# Charging.net
KiCad netlist of a schematic drawn in Altium Designer
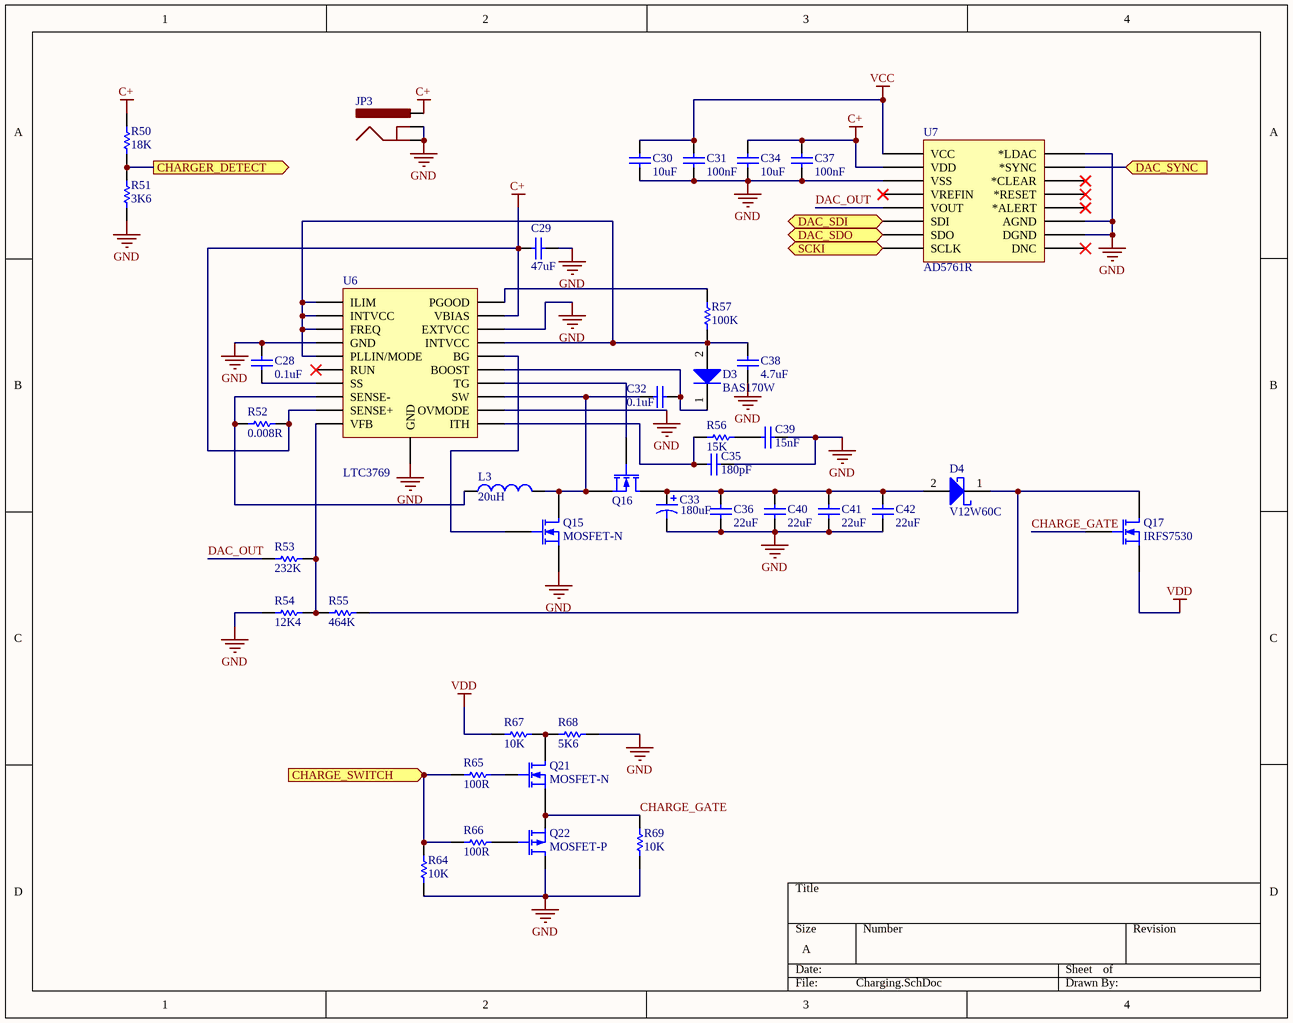
[diagram p0: Charging.SchDoc]

(export (version "E")
  (design (tool "Eeschema 10.0.6"))
  (components
    (comp (ref "C28")
      (value "0.1uF")
      (footprint "CAPC0603(1608)100_N")
      (description "CAP 100nF 6.3V Â±5% 0603 (1608 Metric) Thickness 1mm SMD")
      (fields (field (name "TOLERANCE") "Â±5%"))
      (libsource (lib "Altium Content Vault") (part "CAP"))
    )
    (comp (ref "C29")
      (value "47uF")
      (footprint "CAPC1206(3216)190_N")
      (description "CAP 22uF 25V Â±20% 1206 (3216 Metric) Thickness 1.9mm SMD")
      (fields (field (name "TOLERANCE") "Â±20%"))
      (libsource (lib "Altium Content Vault") (part "CMP-1037-04995-1"))
    )
    (comp (ref "C30")
      (value "10uF")
      (footprint "CAPC0805(2012)145_M")
      (description "CAP 10uF 25V Â±10% 0805 (2012 Metric) Thickness 1.45mm SMD")
      (fields (field (name "TOLERANCE") "Â±10%"))
      (libsource (lib "Altium Content Vault") (part "CAP"))
    )
    (comp (ref "C31")
      (value "100nF")
      (footprint "CAPC0603(1608)100_L")
      (description "CAP 100nF 25V Â±5% 0603 (1608 Metric) Thickness 1mm SMD")
      (fields (field (name "TOLERANCE") "Â±5%"))
      (libsource (lib "Altium Content Vault") (part "CAP"))
    )
    (comp (ref "C32")
      (value "0.1uF")
      (footprint "CAPC0603(1608)100_N")
      (description "CAP 100nF 6.3V Â±5% 0603 (1608 Metric) Thickness 1mm SMD")
      (fields (field (name "TOLERANCE") "Â±5%"))
      (libsource (lib "Altium Content Vault") (part "CAP"))
    )
    (comp (ref "C33")
      (value "180uF")
      (footprint "CAP 180uF 50V")
      (description "Polarized Capacitor (Axial)")
      (fields (field (name "PUBLISHER") "Altium Limited"))
      (libsource (lib "Components") (part "CAP 180uF 50V"))
    )
    (comp (ref "C34")
      (value "10uF")
      (footprint "CAPC0805(2012)145_M")
      (description "CAP 10uF 25V Â±10% 0805 (2012 Metric) Thickness 1.45mm SMD")
      (fields (field (name "TOLERANCE") "Â±10%"))
      (libsource (lib "Altium Content Vault") (part "CAP"))
    )
    (comp (ref "C35")
      (value "180pF")
      (footprint "CAPC0603(1608)100_L")
      (description "CAP 180pF 6.3V Â±5% 0603 (1608 Metric) Thickness 1mm SMD")
      (fields (field (name "TOLERANCE") "Â±5%"))
      (libsource (lib "Altium Content Vault") (part "CAP"))
    )
    (comp (ref "C36")
      (value "22uF")
      (footprint "CAPC2220(5750)230_L")
      (description "CAP 22uF 50V -20% to +80% 2220 (5750 Metric) Thickness 2.2mm SMD")
      (fields (field (name "TOLERANCE") "-20% to +80%"))
      (libsource (lib "Altium Content Vault") (part "CAP"))
    )
    (comp (ref "C37")
      (value "100nF")
      (footprint "CAPC0603(1608)100_L")
      (description "CAP 100nF 25V Â±5% 0603 (1608 Metric) Thickness 1mm SMD")
      (fields (field (name "TOLERANCE") "Â±5%"))
      (libsource (lib "Altium Content Vault") (part "CAP"))
    )
    (comp (ref "C38")
      (value "4.7uF")
      (footprint "CAPC0603(1608)55_L")
      (description "CAP 4.7uF 6.3V Â±10% 0603 (1608 Metric) Thickness 0.55mm SMD")
      (fields (field (name "TOLERANCE") "Â±10%"))
      (libsource (lib "Altium Content Vault") (part "CAP"))
    )
    (comp (ref "C39")
      (value "15nF")
      (footprint "CAPC0603(1608)100_M")
      (description "CAP 15nF 6.3V Â±5% 0603 (1608 Metric) Thickness 1mm SMD")
      (fields (field (name "TOLERANCE") "Â±5%"))
      (libsource (lib "Altium Content Vault") (part "CAP"))
    )
    (comp (ref "C40")
      (value "22uF")
      (footprint "CAPC2220(5750)230_L")
      (description "CAP 22uF 50V -20% to +80% 2220 (5750 Metric) Thickness 2.2mm SMD")
      (fields (field (name "TOLERANCE") "-20% to +80%"))
      (libsource (lib "Altium Content Vault") (part "CAP"))
    )
    (comp (ref "C41")
      (value "22uF")
      (footprint "CAPC2220(5750)230_L")
      (description "CAP 22uF 50V -20% to +80% 2220 (5750 Metric) Thickness 2.2mm SMD")
      (fields (field (name "TOLERANCE") "-20% to +80%"))
      (libsource (lib "Altium Content Vault") (part "CAP"))
    )
    (comp (ref "C42")
      (value "22uF")
      (footprint "CAPC2220(5750)230_L")
      (description "CAP 22uF 50V -20% to +80% 2220 (5750 Metric) Thickness 2.2mm SMD")
      (fields (field (name "TOLERANCE") "-20% to +80%"))
      (libsource (lib "Altium Content Vault") (part "CAP"))
    )
    (comp (ref "D3")
      (value "BAS170W")
      (footprint "INF-SOD323_V")
      (description "Silicon Schottky Diode, -55 to 125 degC, SOD323, Reel, Green")
      (fields (field (name "MANUFACTURER") "Infineon"))
      (libsource (lib "Altium Content Vault") (part "INF-D_K1A2-2"))
    )
    (comp (ref "D4")
      (value "V12W60C")
      (footprint "DPAK229P1003X238-3N")
      (libsource (lib "Components") (part "V12W60C"))
    )
    (comp (ref "JP3")
      (value "~")
      (footprint "POWER_JACK_SMD_OVERPASTE_REDBOARD_0603")
      (libsource (lib "SparkFun-Connectors") (part "POWER_JACK1"))
    )
    (comp (ref "L3")
      (value "20uH")
      (footprint "Inductor_LR")
      (description "Inductor")
      (fields (field (name "PUBLISHER") "Altium Limited"))
      (libsource (lib "Components") (part "CTX20-7-52LP-R"))
    )
    (comp (ref "Q15")
      (value "MOSFET-N")
      (footprint "SOIC127P600X175-8N")
      (description "N-Channel MOSFET")
      (fields (field (name "PUBLISHER") "Altium Limited"))
      (libsource (lib "Components") (part "MOSFET-N"))
    )
    (comp (ref "Q16")
      (value "~")
      (footprint "SOIC127P600X175-8N")
      (description "N-Channel MOSFET")
      (fields (field (name "PUBLISHER") "Altium Limited"))
      (libsource (lib "Components") (part "MOSFET-N"))
    )
    (comp (ref "Q17")
      (value "IRFS7530")
      (footprint "DPAK127P1525X483-7N")
      (description "N-Channel MOSFET")
      (fields (field (name "PUBLISHER") "Altium Limited"))
      (libsource (lib "Components") (part "IRFS7530"))
    )
    (comp (ref "Q21")
      (value "MOSFET-N")
      (footprint "SOT23-3")
      (description "N-Channel MOSFET")
      (fields (field (name "PUBLISHER") "Altium Limited"))
      (libsource (lib "Components") (part "MOSFET-N"))
    )
    (comp (ref "Q22")
      (value "MOSFET-P")
      (footprint "SOT23-3")
      (description "P-Channel MOSFET")
      (fields (field (name "PUBLISHER") "Altium Limited"))
      (libsource (lib "Components") (part "MOSFET-P"))
    )
    (comp (ref "R50")
      (value "18K")
      (footprint "RESC0603(1608)_L")
      (description "18K 0.1W 1% 0603 (1608 Metric)  SMD")
      (fields (field (name "POWER") "0.1 W") (field (name "TOLERANCE") "1 %"))
      (libsource (lib "Altium Content Vault") (part "RES"))
    )
    (comp (ref "R51")
      (value "3K6")
      (footprint "RESC0603(1608)_M")
      (description "3K6 0.1W 1% 0603 (1608 Metric)  SMD")
      (fields (field (name "TOLERANCE") "1 %") (field (name "POWER") "0.1 W"))
      (libsource (lib "Altium Content Vault") (part "RES"))
    )
    (comp (ref "R52")
      (value "0.008R")
      (footprint "RESC2010(5025)_N")
      (description "1R 0.75W 5% 2010 (5025 Metric)  SMD")
      (fields (field (name "TOLERANCE") "5 %") (field (name "POWER") "0.75 W"))
      (libsource (lib "Altium Content Vault") (part "CMP-1017-00002-1"))
    )
    (comp (ref "R53")
      (value "232K")
      (footprint "RESC0603(1608)_L")
      (description "232K 0.1W 1% 0603 (1608 Metric)  SMD")
      (fields (field (name "TOLERANCE") "1 %") (field (name "POWER") "0.1 W"))
      (libsource (lib "Altium Content Vault") (part "RES"))
    )
    (comp (ref "R54")
      (value "12K4")
      (footprint "RESC0603(1608)_L")
      (description "12K4 0.1W 1% 0603 (1608 Metric)  SMD")
      (fields (field (name "POWER") "0.1 W") (field (name "TOLERANCE") "1 %"))
      (libsource (lib "Altium Content Vault") (part "RES"))
    )
    (comp (ref "R55")
      (value "464K")
      (footprint "RESC0603(1608)_N")
      (description "464K 0.1W 1% 0603 (1608 Metric)  SMD")
      (fields (field (name "TOLERANCE") "1 %") (field (name "POWER") "0.1 W"))
      (libsource (lib "Altium Content Vault") (part "RES"))
    )
    (comp (ref "R56")
      (value "15K")
      (footprint "RESC0603(1608)_L")
      (description "15K 0.1W 5% 0603 (1608 Metric)  SMD")
      (fields (field (name "POWER") "0.1 W") (field (name "TOLERANCE") "5 %"))
      (libsource (lib "Altium Content Vault") (part "RES"))
    )
    (comp (ref "R57")
      (value "100K")
      (footprint "RESC0603(1608)_M")
      (description "100K 0.1W 5% 0603 (1608 Metric)  SMD")
      (fields (field (name "TOLERANCE") "5 %") (field (name "POWER") "0.1 W"))
      (libsource (lib "Altium Content Vault") (part "RES"))
    )
    (comp (ref "R64")
      (value "10K")
      (footprint "RESC0603(1608)_M")
      (description "10K 0.1W 1% 0603 (1608 Metric)  SMD")
      (fields (field (name "POWER") "0.1 W") (field (name "TOLERANCE") "1 %"))
      (libsource (lib "Altium Content Vault") (part "RES"))
    )
    (comp (ref "R65")
      (value "100R")
      (footprint "RESC0603(1608)_M")
      (description "100R 0.1W 5% 0603 (1608 Metric)  SMD")
      (fields (field (name "TOLERANCE") "5 %") (field (name "POWER") "0.1 W"))
      (libsource (lib "Altium Content Vault") (part "RES"))
    )
    (comp (ref "R66")
      (value "100R")
      (footprint "RESC0603(1608)_M")
      (description "100R 0.1W 5% 0603 (1608 Metric)  SMD")
      (fields (field (name "TOLERANCE") "5 %") (field (name "POWER") "0.1 W"))
      (libsource (lib "Altium Content Vault") (part "RES"))
    )
    (comp (ref "R67")
      (value "10K")
      (footprint "RESC0603(1608)_M")
      (description "10K 0.1W 5% 0603 (1608 Metric)  SMD")
      (fields (field (name "TOLERANCE") "5 %") (field (name "POWER") "0.1 W"))
      (libsource (lib "Altium Content Vault") (part "RES"))
    )
    (comp (ref "R68")
      (value "5K6")
      (footprint "RESC0603(1608)_N")
      (description "5K6 0.1W 1% 0603 (1608 Metric)  SMD")
      (fields (field (name "TOLERANCE") "1 %") (field (name "POWER") "0.1 W"))
      (libsource (lib "Altium Content Vault") (part "RES"))
    )
    (comp (ref "R69")
      (value "10K")
      (footprint "RESC0603(1608)_M")
      (description "10K 0.1W 1% 0603 (1608 Metric)  SMD")
      (fields (field (name "POWER") "0.1 W") (field (name "TOLERANCE") "1 %"))
      (libsource (lib "Altium Content Vault") (part "RES"))
    )
    (comp (ref "U6")
      (value "LTC3769")
      (footprint "TSOP65P640X120_HS-21N")
      (libsource (lib "Components") (part "LTC3769"))
    )
    (comp (ref "U7")
      (value "AD5761R")
      (footprint "RU_16")
      (description "Imported")
      (libsource (lib "Components") (part "AD5761BRUZ"))
    )
  )
  (nets
    (net (code "1") (name "/CHARGER_DETECT") (class "Default")
      (node (ref "R50") (pin "1") (pinfunction "1_1") (pintype "passive"))
      (node (ref "R51") (pin "2") (pinfunction "2_2") (pintype "passive"))
    )
    (net (code "2") (name "/CHARGE_GATE") (class "Default")
      (node (ref "Q17") (pin "2") (pinfunction "G_2") (pintype "passive"))
      (node (ref "Q21") (pin "3") (pinfunction "S_3") (pintype "passive"))
      (node (ref "Q22") (pin "3") (pinfunction "S_3") (pintype "passive"))
      (node (ref "R69") (pin "2") (pinfunction "2_2") (pintype "passive"))
    )
    (net (code "3") (name "/CHARGE_SWITCH") (class "Default")
      (node (ref "R64") (pin "2") (pinfunction "2_2") (pintype "passive"))
      (node (ref "R65") (pin "1") (pinfunction "1_1") (pintype "passive"))
      (node (ref "R66") (pin "1") (pinfunction "1_1") (pintype "passive"))
    )
    (net (code "4") (name "/DAC_OUT") (class "Default")
      (node (ref "R53") (pin "1") (pinfunction "1_1") (pintype "passive"))
      (node (ref "U7") (pin "7") (pinfunction "VOUT_7") (pintype "passive"))
    )
    (net (code "5") (name "/DAC_SDI") (class "Default")
      (node (ref "U7") (pin "12") (pinfunction "SDI_12") (pintype "passive"))
    )
    (net (code "6") (name "/DAC_SDO") (class "Default")
      (node (ref "U7") (pin "10") (pinfunction "SDO_10") (pintype "passive"))
    )
    (net (code "7") (name "/DAC_SYNC") (class "Default")
      (node (ref "U7") (pin "13") (pinfunction "*SYNC_13") (pintype "passive"))
    )
    (net (code "8") (name "/SCKI") (class "Default")
      (node (ref "U7") (pin "14") (pinfunction "SCLK_14") (pintype "passive"))
    )
    (net (code "9") (name "C+") (class "Default")
      (node (ref "C29") (pin "1") (pinfunction "1_1") (pintype "passive"))
      (node (ref "C34") (pin "2") (pinfunction "2_2") (pintype "passive"))
      (node (ref "C37") (pin "2") (pinfunction "2_2") (pintype "passive"))
      (node (ref "JP3") (pin "VIN0") (pinfunction "PWR_VIN0") (pintype "passive"))
      (node (ref "R50") (pin "2") (pinfunction "2_2") (pintype "passive"))
      (node (ref "R52") (pin "2") (pinfunction "2_2") (pintype "passive"))
      (node (ref "U6") (pin "19") (pinfunction "VBIAS_19") (pintype "passive"))
      (node (ref "U6") (pin "9") (pinfunction "SENSE+_9") (pintype "passive"))
      (node (ref "U7") (pin "8") (pinfunction "VDD_8") (pintype "passive"))
    )
    (net (code "10") (name "GND") (class "Default")
      (node (ref "C28") (pin "2") (pinfunction "2_2") (pintype "passive"))
      (node (ref "C29") (pin "2") (pinfunction "2_2") (pintype "passive"))
      (node (ref "C30") (pin "1") (pinfunction "1_1") (pintype "passive"))
      (node (ref "C31") (pin "1") (pinfunction "1_1") (pintype "passive"))
      (node (ref "C33") (pin "2") (pinfunction "2_2") (pintype "passive"))
      (node (ref "C34") (pin "1") (pinfunction "1_1") (pintype "passive"))
      (node (ref "C35") (pin "2") (pinfunction "2_2") (pintype "passive"))
      (node (ref "C36") (pin "1") (pinfunction "1_1") (pintype "passive"))
      (node (ref "C37") (pin "1") (pinfunction "1_1") (pintype "passive"))
      (node (ref "C38") (pin "1") (pinfunction "1_1") (pintype "passive"))
      (node (ref "C39") (pin "2") (pinfunction "2_2") (pintype "passive"))
      (node (ref "C40") (pin "1") (pinfunction "1_1") (pintype "passive"))
      (node (ref "C41") (pin "1") (pinfunction "1_1") (pintype "passive"))
      (node (ref "C42") (pin "1") (pinfunction "1_1") (pintype "passive"))
      (node (ref "JP3") (pin "GND") (pinfunction "GNDBREAK_GND") (pintype "passive"))
      (node (ref "JP3") (pin "P$4") (pinfunction "GND_P$4") (pintype "passive"))
      (node (ref "Q15") (pin "3") (pinfunction "S_3") (pintype "passive"))
      (node (ref "Q22") (pin "2") (pinfunction "D_2") (pintype "passive"))
      (node (ref "R51") (pin "1") (pinfunction "1_1") (pintype "passive"))
      (node (ref "R54") (pin "1") (pinfunction "1_1") (pintype "passive"))
      (node (ref "R64") (pin "1") (pinfunction "1_1") (pintype "passive"))
      (node (ref "R68") (pin "1") (pinfunction "1_1") (pintype "passive"))
      (node (ref "R69") (pin "1") (pinfunction "1_1") (pintype "passive"))
      (node (ref "U6") (pin "12") (pinfunction "OVMODE_12") (pintype "passive"))
      (node (ref "U6") (pin "18") (pinfunction "EXTVCC_18") (pintype "passive"))
      (node (ref "U6") (pin "21") (pinfunction "GND_21") (pintype "passive"))
      (node (ref "U6") (pin "4") (pinfunction "GND_4") (pintype "passive"))
      (node (ref "U7") (pin "11") (pinfunction "*LDAC_11") (pintype "passive"))
      (node (ref "U7") (pin "16") (pinfunction "DGND_16") (pintype "passive"))
      (node (ref "U7") (pin "5") (pinfunction "AGND_5") (pintype "passive"))
      (node (ref "U7") (pin "6") (pinfunction "VSS_6") (pintype "passive"))
    )
    (net (code "11") (name "Net-(C39-Pad1)") (class "Default")
      (node (ref "C39") (pin "1") (pinfunction "1_1") (pintype "passive"))
      (node (ref "R56") (pin "2") (pinfunction "2_2") (pintype "passive"))
    )
    (net (code "12") (name "Net-(D3-A)") (class "Default")
      (node (ref "C38") (pin "2") (pinfunction "2_2") (pintype "passive"))
      (node (ref "D3") (pin "2") (pinfunction "A_2") (pintype "passive"))
      (node (ref "R57") (pin "1") (pinfunction "1_1") (pintype "passive"))
      (node (ref "U6") (pin "1") (pinfunction "ILIM_1") (pintype "passive"))
      (node (ref "U6") (pin "17") (pinfunction "INTVCC_17") (pintype "passive"))
      (node (ref "U6") (pin "2") (pinfunction "INTVCC_2") (pintype "passive"))
      (node (ref "U6") (pin "3") (pinfunction "FREQ_3") (pintype "passive"))
      (node (ref "U6") (pin "5") (pinfunction "PLLIN/MODE_5") (pintype "passive"))
    )
    (net (code "13") (name "Net-(D3-K)") (class "Default")
      (node (ref "C32") (pin "2") (pinfunction "2_2") (pintype "passive"))
      (node (ref "D3") (pin "1") (pinfunction "K_1") (pintype "passive"))
      (node (ref "U6") (pin "15") (pinfunction "BOOST_15") (pintype "passive"))
    )
    (net (code "14") (name "Net-(D4-A)") (class "Default")
      (node (ref "C33") (pin "1") (pinfunction "1_1") (pintype "passive"))
      (node (ref "C36") (pin "2") (pinfunction "2_2") (pintype "passive"))
      (node (ref "C40") (pin "2") (pinfunction "2_2") (pintype "passive"))
      (node (ref "C41") (pin "2") (pinfunction "2_2") (pintype "passive"))
      (node (ref "C42") (pin "2") (pinfunction "2_2") (pintype "passive"))
      (node (ref "D4") (pin "2") (pinfunction "A_2") (pintype "passive"))
      (node (ref "Q16") (pin "2") (pinfunction "D_2") (pintype "passive"))
    )
    (net (code "15") (name "Net-(D4-K)") (class "Default")
      (node (ref "D4") (pin "1") (pinfunction "K_1") (pintype "passive"))
      (node (ref "Q17") (pin "1") (pinfunction "D_1") (pintype "passive"))
      (node (ref "R55") (pin "2") (pinfunction "2_2") (pintype "passive"))
    )
    (net (code "16") (name "Net-(Q15-D)") (class "Default")
      (node (ref "C32") (pin "1") (pinfunction "1_1") (pintype "passive"))
      (node (ref "L3") (pin "2") (pinfunction "2_2") (pintype "passive"))
      (node (ref "Q15") (pin "2") (pinfunction "D_2") (pintype "passive"))
      (node (ref "Q16") (pin "3") (pinfunction "S_3") (pintype "passive"))
      (node (ref "U6") (pin "13") (pinfunction "SW_13") (pintype "passive"))
    )
    (net (code "17") (name "Net-(Q15-G)") (class "Default")
      (node (ref "Q15") (pin "1") (pinfunction "G_1") (pintype "passive"))
      (node (ref "U6") (pin "16") (pinfunction "BG_16") (pintype "passive"))
    )
    (net (code "18") (name "Net-(Q16-G)") (class "Default")
      (node (ref "Q16") (pin "1") (pinfunction "G_1") (pintype "passive"))
      (node (ref "U6") (pin "14") (pinfunction "TG_14") (pintype "passive"))
    )
    (net (code "19") (name "Net-(Q21-D)") (class "Default")
      (node (ref "Q21") (pin "2") (pinfunction "D_2") (pintype "passive"))
      (node (ref "R67") (pin "1") (pinfunction "1_1") (pintype "passive"))
      (node (ref "R68") (pin "2") (pinfunction "2_2") (pintype "passive"))
    )
    (net (code "20") (name "Net-(Q21-G)") (class "Default")
      (node (ref "Q21") (pin "1") (pinfunction "G_1") (pintype "passive"))
      (node (ref "R65") (pin "2") (pinfunction "2_2") (pintype "passive"))
    )
    (net (code "21") (name "Net-(Q22-G)") (class "Default")
      (node (ref "Q22") (pin "1") (pinfunction "G_1") (pintype "passive"))
      (node (ref "R66") (pin "2") (pinfunction "2_2") (pintype "passive"))
    )
    (net (code "22") (name "Net-(U6-ITH)") (class "Default")
      (node (ref "C35") (pin "1") (pinfunction "1_1") (pintype "passive"))
      (node (ref "R56") (pin "1") (pinfunction "1_1") (pintype "passive"))
      (node (ref "U6") (pin "11") (pinfunction "ITH_11") (pintype "passive"))
    )
    (net (code "23") (name "Net-(U6-PGOOD)") (class "Default")
      (node (ref "R57") (pin "2") (pinfunction "2_2") (pintype "passive"))
      (node (ref "U6") (pin "20") (pinfunction "PGOOD_20") (pintype "passive"))
    )
    (net (code "24") (name "Net-(U6-SENSE-)") (class "Default")
      (node (ref "L3") (pin "1") (pinfunction "1_1") (pintype "passive"))
      (node (ref "R52") (pin "1") (pinfunction "1_1") (pintype "passive"))
      (node (ref "U6") (pin "8") (pinfunction "SENSE-_8") (pintype "passive"))
    )
    (net (code "25") (name "Net-(U6-SS)") (class "Default")
      (node (ref "C28") (pin "1") (pinfunction "1_1") (pintype "passive"))
      (node (ref "U6") (pin "7") (pinfunction "SS_7") (pintype "passive"))
    )
    (net (code "26") (name "Net-(U6-VFB)") (class "Default")
      (node (ref "R53") (pin "2") (pinfunction "2_2") (pintype "passive"))
      (node (ref "R54") (pin "2") (pinfunction "2_2") (pintype "passive"))
      (node (ref "R55") (pin "1") (pinfunction "1_1") (pintype "passive"))
      (node (ref "U6") (pin "10") (pinfunction "VFB_10") (pintype "passive"))
    )
    (net (code "27") (name "VCC") (class "Default")
      (node (ref "C30") (pin "2") (pinfunction "2_2") (pintype "passive"))
      (node (ref "C31") (pin "2") (pinfunction "2_2") (pintype "passive"))
      (node (ref "U7") (pin "15") (pinfunction "VCC_15") (pintype "passive"))
    )
    (net (code "28") (name "VDD") (class "Default")
      (node (ref "Q17") (pin "3") (pinfunction "S_3") (pintype "passive"))
      (node (ref "R67") (pin "2") (pinfunction "2_2") (pintype "passive"))
    )
    (net (code "29") (name "unconnected-(U6-RUN-Pad6)") (class "Default")
      (node (ref "U6") (pin "6") (pinfunction "RUN_6") (pintype "passive+no_connect"))
    )
    (net (code "30") (name "unconnected-(U7-*ALERT-Pad1)") (class "Default")
      (node (ref "U7") (pin "1") (pinfunction "*ALERT_1") (pintype "passive+no_connect"))
    )
    (net (code "31") (name "unconnected-(U7-*CLEAR-Pad2)") (class "Default")
      (node (ref "U7") (pin "2") (pinfunction "*CLEAR_2") (pintype "passive+no_connect"))
    )
    (net (code "32") (name "unconnected-(U7-*RESET-Pad3)") (class "Default")
      (node (ref "U7") (pin "3") (pinfunction "*RESET_3") (pintype "passive+no_connect"))
    )
    (net (code "33") (name "unconnected-(U7-DNC-Pad9)") (class "Default")
      (node (ref "U7") (pin "9") (pinfunction "DNC_9") (pintype "passive+no_connect"))
    )
    (net (code "34") (name "unconnected-(U7-VREFIN-Pad4)") (class "Default")
      (node (ref "U7") (pin "4") (pinfunction "VREFIN_4") (pintype "passive+no_connect"))
    )
  )
)
